# ST_LINK.net
KiCad netlist of a schematic drawn in Altium Designer
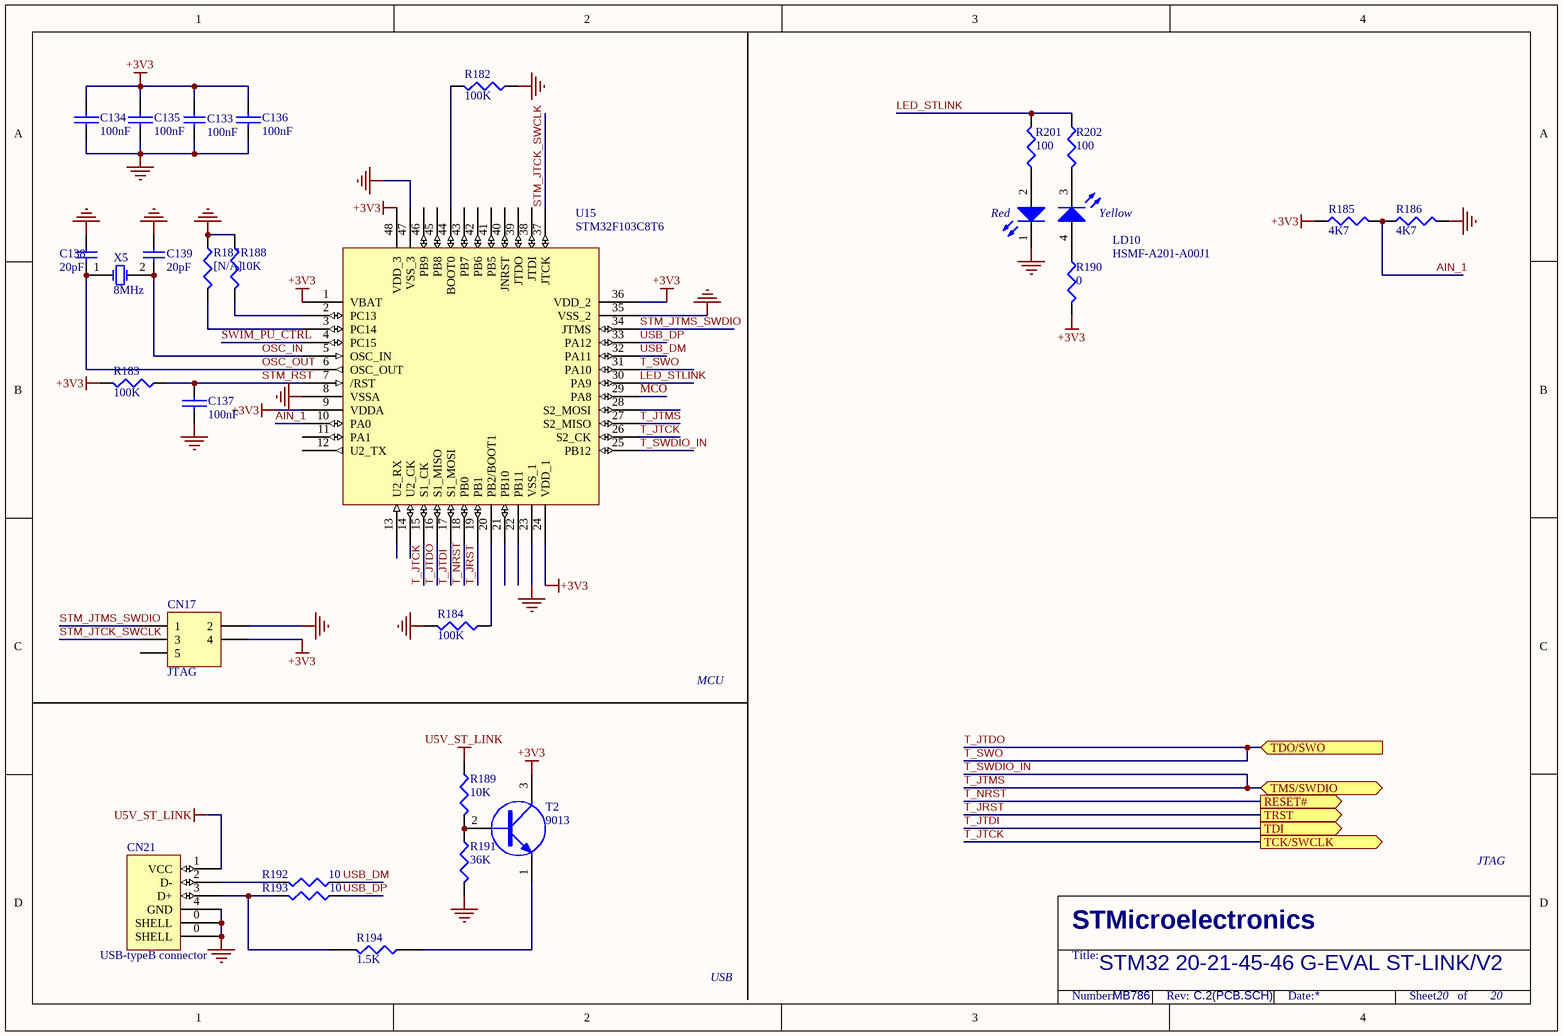
[diagram p0: ST_LINK.SCHDOC]

(export (version "E")
  (design (tool "Eeschema 10.0.6"))
  (components
    (comp (ref "C133")
      (value "100nF")
      (footprint "0402C")
      (description "Capacitor")
      (fields (field (name "PUBLISHER") "Altium Limited"))
      (libsource (lib "*") (part "Cap"))
    )
    (comp (ref "C134") (value "100nF") (footprint "0402C") (libsource (lib "*") (part "CAP")))
    (comp (ref "C135") (value "100nF") (footprint "0402C") (libsource (lib "*") (part "CAP")))
    (comp (ref "C136") (value "100nF") (footprint "0402C") (libsource (lib "*") (part "CAP")))
    (comp (ref "C137") (value "100nF") (footprint "0402C") (libsource (lib "*") (part "CAP")))
    (comp (ref "C138")
      (value "20pF")
      (footprint "0603C")
      (description "Capacitor")
      (fields (field (name "Comment") "Cap") (field (name "PUBLISHER") "Altium Limited"))
      (libsource (lib "*") (part "Cap"))
    )
    (comp (ref "C139")
      (value "20pF")
      (footprint "0603C")
      (description "Capacitor")
      (fields (field (name "Comment") "Cap") (field (name "PUBLISHER") "Altium Limited"))
      (libsource (lib "*") (part "Cap"))
    )
    (comp (ref "CN17")
      (value "JTAG")
      (footprint "HDR2X3")
      (description "Header, 3-Pin, Dual row")
      (fields (field (name "PUBLISHER") "Altium Limited"))
      (libsource (lib "Miscellaneous Connectors") (part "Header 3X2"))
    )
    (comp (ref "CN21")
      (value "USB-typeB connector")
      (footprint "USB-B")
      (libsource (lib "*") (part "USB-typeB connector"))
    )
    (comp (ref "LD10") (value "HSMF-A201-A00J1") (libsource (lib "MB819") (part "HSMF-A201-A00J1")))
    (comp (ref "R182") (value "100K") (footprint "0402R") (libsource (lib "*") (part "RES1")))
    (comp (ref "R183") (value "100K") (footprint "0402R") (libsource (lib "*") (part "RES1")))
    (comp (ref "R184") (value "100K") (footprint "0402R") (libsource (lib "*") (part "RES1")))
    (comp (ref "R185") (value "4K7") (footprint "0402R") (libsource (lib "*") (part "RES1")))
    (comp (ref "R186") (value "4K7") (footprint "0402R") (libsource (lib "*") (part "RES1")))
    (comp (ref "R187") (value "[N/A]") (footprint "0603R") (libsource (lib "*") (part "R")))
    (comp (ref "R188") (value "10K") (footprint "0402R") (libsource (lib "*") (part "R")))
    (comp (ref "R189") (value "10K") (footprint "0402R") (libsource (lib "*") (part "R")))
    (comp (ref "R190") (value "0") (footprint "0603R") (libsource (lib "*") (part "RES1")))
    (comp (ref "R191") (value "36K") (footprint "0603R") (libsource (lib "*") (part "R")))
    (comp (ref "R192") (value "10") (footprint "0603R") (libsource (lib "*") (part "RES1")))
    (comp (ref "R193") (value "10") (footprint "0603R") (libsource (lib "*") (part "RES1")))
    (comp (ref "R194") (value "1.5K") (footprint "0603R") (libsource (lib "") (part "RES1_1")))
    (comp (ref "R201") (value "100") (footprint "0603R") (libsource (lib "*") (part "RES1")))
    (comp (ref "R202") (value "100") (footprint "0603R") (libsource (lib "*") (part "RES1")))
    (comp (ref "T2") (value "9013") (footprint "SOT-23") (libsource (lib "*") (part "NPN")))
    (comp (ref "U15")
      (value "STM32F103C8T6")
      (footprint "LQFP48")
      (libsource (lib "*") (part "STM32F10x(48pin)"))
    )
    (comp (ref "X5")
      (value "8MHz")
      (footprint "SMT_XTAL")
      (description "Crystal Oscillator")
      (fields (field (name "PUBLISHER") "Altium Limited"))
      (libsource (lib "*") (part "XTAL"))
    )
  )
  (nets
    (net (code "1") (name "+3V3") (class "Default")
      (node (ref "C133") (pin "1") (pinfunction "1_1") (pintype "passive"))
      (node (ref "C134") (pin "2") (pinfunction "2_2") (pintype "passive"))
      (node (ref "C135") (pin "2") (pinfunction "2_2") (pintype "passive"))
      (node (ref "C136") (pin "2") (pinfunction "2_2") (pintype "passive"))
      (node (ref "CN17") (pin "4") (pinfunction "4_4") (pintype "passive"))
      (node (ref "R183") (pin "2") (pinfunction "2_2") (pintype "passive"))
      (node (ref "R185") (pin "1") (pinfunction "1_1") (pintype "passive"))
      (node (ref "R190") (pin "2") (pinfunction "2_2") (pintype "passive"))
      (node (ref "T2") (pin "3") (pinfunction "C_3") (pintype "passive"))
      (node (ref "U15") (pin "1") (pinfunction "VBAT_1") (pintype "power_in"))
      (node (ref "U15") (pin "24") (pinfunction "VDD_1_24") (pintype "power_in"))
      (node (ref "U15") (pin "36") (pinfunction "VDD_2_36") (pintype "power_in"))
      (node (ref "U15") (pin "48") (pinfunction "VDD_3_48") (pintype "power_in"))
      (node (ref "U15") (pin "9") (pinfunction "VDDA_9") (pintype "power_in"))
    )
    (net (code "2") (name "/AIN_1") (class "Default")
      (node (ref "R185") (pin "2") (pinfunction "2_2") (pintype "passive"))
      (node (ref "R186") (pin "1") (pinfunction "1_1") (pintype "passive"))
      (node (ref "U15") (pin "10") (pinfunction "PA0_10") (pintype "bidirectional"))
    )
    (net (code "3") (name "/LED_STLINK") (class "Default")
      (node (ref "R201") (pin "2") (pinfunction "2_2") (pintype "passive"))
      (node (ref "R202") (pin "1") (pinfunction "1_1") (pintype "passive"))
      (node (ref "U15") (pin "30") (pinfunction "PA9_30") (pintype "bidirectional"))
    )
    (net (code "4") (name "/MCO") (class "Default")
      (node (ref "U15") (pin "29") (pinfunction "PA8_29") (pintype "bidirectional"))
    )
    (net (code "5") (name "/OSC_IN") (class "Default")
      (node (ref "C139") (pin "2") (pinfunction "2_2") (pintype "passive"))
      (node (ref "U15") (pin "5") (pinfunction "OSC_IN_5") (pintype "input"))
      (node (ref "X5") (pin "2") (pinfunction "OSC2_2") (pintype "passive"))
    )
    (net (code "6") (name "/OSC_OUT") (class "Default")
      (node (ref "C138") (pin "2") (pinfunction "2_2") (pintype "passive"))
      (node (ref "U15") (pin "6") (pinfunction "OSC_OUT_6") (pintype "output"))
      (node (ref "X5") (pin "1") (pinfunction "OSC1_1") (pintype "passive"))
    )
    (net (code "7") (name "/STM_JTCK_SWCLK") (class "Default")
      (node (ref "CN17") (pin "3") (pinfunction "3_3") (pintype "passive"))
      (node (ref "U15") (pin "37") (pinfunction "JTCK_37") (pintype "bidirectional"))
    )
    (net (code "8") (name "/STM_JTMS_SWDIO") (class "Default")
      (node (ref "CN17") (pin "1") (pinfunction "1_1") (pintype "passive"))
      (node (ref "U15") (pin "34") (pinfunction "JTMS_34") (pintype "bidirectional"))
    )
    (net (code "9") (name "/STM_RST") (class "Default")
      (node (ref "C137") (pin "2") (pinfunction "2_2") (pintype "passive"))
      (node (ref "R183") (pin "1") (pinfunction "1_1") (pintype "passive"))
      (node (ref "U15") (pin "7") (pinfunction "/RST_7") (pintype "input"))
    )
    (net (code "10") (name "/SWIM_PU_CTRL") (class "Default")
      (node (ref "U15") (pin "4") (pinfunction "PC15_4") (pintype "bidirectional"))
    )
    (net (code "11") (name "/T_JRST") (class "Default")
      (node (ref "U15") (pin "19") (pinfunction "PB1_19") (pintype "bidirectional"))
    )
    (net (code "12") (name "/T_JTCK") (class "Default")
      (node (ref "U15") (pin "15") (pinfunction "S1_CK_15") (pintype "bidirectional"))
      (node (ref "U15") (pin "26") (pinfunction "S2_CK_26") (pintype "bidirectional"))
    )
    (net (code "13") (name "/T_JTDI") (class "Default")
      (node (ref "U15") (pin "17") (pinfunction "S1_MOSI_17") (pintype "bidirectional"))
    )
    (net (code "14") (name "/T_JTDO") (class "Default")
      (node (ref "U15") (pin "16") (pinfunction "S1_MISO_16") (pintype "bidirectional"))
      (node (ref "U15") (pin "31") (pinfunction "PA10_31") (pintype "bidirectional"))
    )
    (net (code "15") (name "/T_JTMS") (class "Default")
      (node (ref "U15") (pin "25") (pinfunction "PB12_25") (pintype "bidirectional"))
      (node (ref "U15") (pin "27") (pinfunction "S2_MISO_27") (pintype "bidirectional"))
    )
    (net (code "16") (name "/T_NRST") (class "Default")
      (node (ref "U15") (pin "18") (pinfunction "PB0_18") (pintype "bidirectional"))
    )
    (net (code "17") (name "/USB_DM") (class "Default")
      (node (ref "R192") (pin "1") (pinfunction "1_1") (pintype "passive"))
      (node (ref "U15") (pin "32") (pinfunction "PA11_32") (pintype "bidirectional"))
    )
    (net (code "18") (name "/USB_DP") (class "Default")
      (node (ref "R193") (pin "1") (pinfunction "1_1") (pintype "passive"))
      (node (ref "U15") (pin "33") (pinfunction "PA12_33") (pintype "bidirectional"))
    )
    (net (code "19") (name "GND") (class "Default")
      (node (ref "C133") (pin "2") (pinfunction "2_2") (pintype "passive"))
      (node (ref "C134") (pin "1") (pinfunction "1_1") (pintype "passive"))
      (node (ref "C135") (pin "1") (pinfunction "1_1") (pintype "passive"))
      (node (ref "C136") (pin "1") (pinfunction "1_1") (pintype "passive"))
      (node (ref "C137") (pin "1") (pinfunction "1_1") (pintype "passive"))
      (node (ref "C138") (pin "1") (pinfunction "1_1") (pintype "passive"))
      (node (ref "C139") (pin "1") (pinfunction "1_1") (pintype "passive"))
      (node (ref "CN17") (pin "2") (pinfunction "2_2") (pintype "passive"))
      (node (ref "CN21") (pin "0") (pinfunction "SHELL_0") (pintype "power_in"))
      (node (ref "CN21") (pin "4") (pinfunction "GND_4") (pintype "passive"))
      (node (ref "LD10") (pin "1") (pinfunction "RED_cathode_1") (pintype "passive"))
      (node (ref "R182") (pin "1") (pinfunction "1_1") (pintype "passive"))
      (node (ref "R184") (pin "2") (pinfunction "2_2") (pintype "passive"))
      (node (ref "R186") (pin "2") (pinfunction "2_2") (pintype "passive"))
      (node (ref "R187") (pin "1") (pinfunction "1_1") (pintype "passive"))
      (node (ref "R188") (pin "1") (pinfunction "1_1") (pintype "passive"))
      (node (ref "R191") (pin "2") (pinfunction "2_2") (pintype "passive"))
      (node (ref "U15") (pin "23") (pinfunction "VSS_1_23") (pintype "passive"))
      (node (ref "U15") (pin "35") (pinfunction "VSS_2_35") (pintype "passive"))
      (node (ref "U15") (pin "47") (pinfunction "VSS_3_47") (pintype "passive"))
      (node (ref "U15") (pin "8") (pinfunction "VSSA_8") (pintype "passive"))
    )
    (net (code "20") (name "Net-(CN21-D+)") (class "Default")
      (node (ref "CN21") (pin "3") (pinfunction "D+_3") (pintype "bidirectional"))
      (node (ref "R193") (pin "2") (pinfunction "2_2") (pintype "passive"))
      (node (ref "R194") (pin "2") (pinfunction "2_2") (pintype "passive"))
    )
    (net (code "21") (name "Net-(CN21-D-)") (class "Default")
      (node (ref "CN21") (pin "2") (pinfunction "D-_2") (pintype "bidirectional"))
      (node (ref "R192") (pin "2") (pinfunction "2_2") (pintype "passive"))
    )
    (net (code "22") (name "Net-(LD10-Red_anode)") (class "Default")
      (node (ref "LD10") (pin "2") (pinfunction "Red_anode_2") (pintype "passive"))
      (node (ref "R201") (pin "1") (pinfunction "1_1") (pintype "passive"))
    )
    (net (code "23") (name "Net-(LD10-YellowGreen_anode)") (class "Default")
      (node (ref "LD10") (pin "4") (pinfunction "YellowGreen_anode_4") (pintype "passive"))
      (node (ref "R190") (pin "1") (pinfunction "1_1") (pintype "passive"))
    )
    (net (code "24") (name "Net-(LD10-YellowGreen_cathode)") (class "Default")
      (node (ref "LD10") (pin "3") (pinfunction "YellowGreen_cathode_3") (pintype "passive"))
      (node (ref "R202") (pin "2") (pinfunction "2_2") (pintype "passive"))
    )
    (net (code "25") (name "Net-(T2-B)") (class "Default")
      (node (ref "R189") (pin "2") (pinfunction "2_2") (pintype "passive"))
      (node (ref "R191") (pin "1") (pinfunction "1_1") (pintype "passive"))
      (node (ref "T2") (pin "2") (pinfunction "B_2") (pintype "passive"))
    )
    (net (code "26") (name "Net-(T2-E)") (class "Default")
      (node (ref "R194") (pin "1") (pinfunction "1_1") (pintype "passive"))
      (node (ref "T2") (pin "1") (pinfunction "E_1") (pintype "passive"))
    )
    (net (code "27") (name "Net-(U15-BOOT0)") (class "Default")
      (node (ref "R182") (pin "2") (pinfunction "2_2") (pintype "passive"))
      (node (ref "U15") (pin "44") (pinfunction "BOOT0_44") (pintype "bidirectional"))
    )
    (net (code "28") (name "Net-(U15-PB2{slash}BOOT1)") (class "Default")
      (node (ref "R184") (pin "1") (pinfunction "1_1") (pintype "passive"))
      (node (ref "U15") (pin "20") (pinfunction "PB2/BOOT1_20") (pintype "passive"))
    )
    (net (code "29") (name "Net-(U15-PC13)") (class "Default")
      (node (ref "R188") (pin "2") (pinfunction "2_2") (pintype "passive"))
      (node (ref "U15") (pin "2") (pinfunction "PC13_2") (pintype "bidirectional"))
    )
    (net (code "30") (name "Net-(U15-PC14)") (class "Default")
      (node (ref "R187") (pin "2") (pinfunction "2_2") (pintype "passive"))
      (node (ref "U15") (pin "3") (pinfunction "PC14_3") (pintype "bidirectional"))
    )
    (net (code "31") (name "U5V_ST_LINK") (class "Default")
      (node (ref "CN21") (pin "1") (pinfunction "VCC_1") (pintype "bidirectional"))
      (node (ref "R189") (pin "1") (pinfunction "1_1") (pintype "passive"))
    )
    (net (code "32") (name "unconnected-(CN17-Pad5)") (class "Default")
      (node (ref "CN17") (pin "5") (pinfunction "5_5") (pintype "passive"))
    )
    (net (code "33") (name "unconnected-(U15-JNRST-Pad40)") (class "Default")
      (node (ref "U15") (pin "40") (pinfunction "JNRST_40") (pintype "bidirectional"))
    )
    (net (code "34") (name "unconnected-(U15-JTDI-Pad38)") (class "Default")
      (node (ref "U15") (pin "38") (pinfunction "JTDI_38") (pintype "bidirectional"))
    )
    (net (code "35") (name "unconnected-(U15-JTDO-Pad39)") (class "Default")
      (node (ref "U15") (pin "39") (pinfunction "JTDO_39") (pintype "bidirectional"))
    )
    (net (code "36") (name "unconnected-(U15-PA1-Pad11)") (class "Default")
      (node (ref "U15") (pin "11") (pinfunction "PA1_11") (pintype "bidirectional"))
    )
    (net (code "37") (name "unconnected-(U15-PB5-Pad41)") (class "Default")
      (node (ref "U15") (pin "41") (pinfunction "PB5_41") (pintype "bidirectional"))
    )
    (net (code "38") (name "unconnected-(U15-PB6-Pad42)") (class "Default")
      (node (ref "U15") (pin "42") (pinfunction "PB6_42") (pintype "bidirectional"))
    )
    (net (code "39") (name "unconnected-(U15-PB7-Pad43)") (class "Default")
      (node (ref "U15") (pin "43") (pinfunction "PB7_43") (pintype "bidirectional"))
    )
    (net (code "40") (name "unconnected-(U15-PB8-Pad45)") (class "Default")
      (node (ref "U15") (pin "45") (pinfunction "PB8_45") (pintype "bidirectional"))
    )
    (net (code "41") (name "unconnected-(U15-PB9-Pad46)") (class "Default")
      (node (ref "U15") (pin "46") (pinfunction "PB9_46") (pintype "bidirectional"))
    )
    (net (code "42") (name "unconnected-(U15-PB10-Pad21)") (class "Default")
      (node (ref "U15") (pin "21") (pinfunction "PB10_21") (pintype "bidirectional"))
    )
    (net (code "43") (name "unconnected-(U15-PB11-Pad22)") (class "Default")
      (node (ref "U15") (pin "22") (pinfunction "PB11_22") (pintype "passive"))
    )
    (net (code "44") (name "unconnected-(U15-S2_MOSI-Pad28)") (class "Default")
      (node (ref "U15") (pin "28") (pinfunction "S2_MOSI_28") (pintype "bidirectional"))
    )
    (net (code "45") (name "unconnected-(U15-U2_CK-Pad14)") (class "Default")
      (node (ref "U15") (pin "14") (pinfunction "U2_CK_14") (pintype "bidirectional"))
    )
    (net (code "46") (name "unconnected-(U15-U2_RX-Pad13)") (class "Default")
      (node (ref "U15") (pin "13") (pinfunction "U2_RX_13") (pintype "input"))
    )
    (net (code "47") (name "unconnected-(U15-U2_TX-Pad12)") (class "Default")
      (node (ref "U15") (pin "12") (pinfunction "U2_TX_12") (pintype "output"))
    )
  )
)
